# clock2x.net
KiCad netlist of a schematic drawn in EAGLE
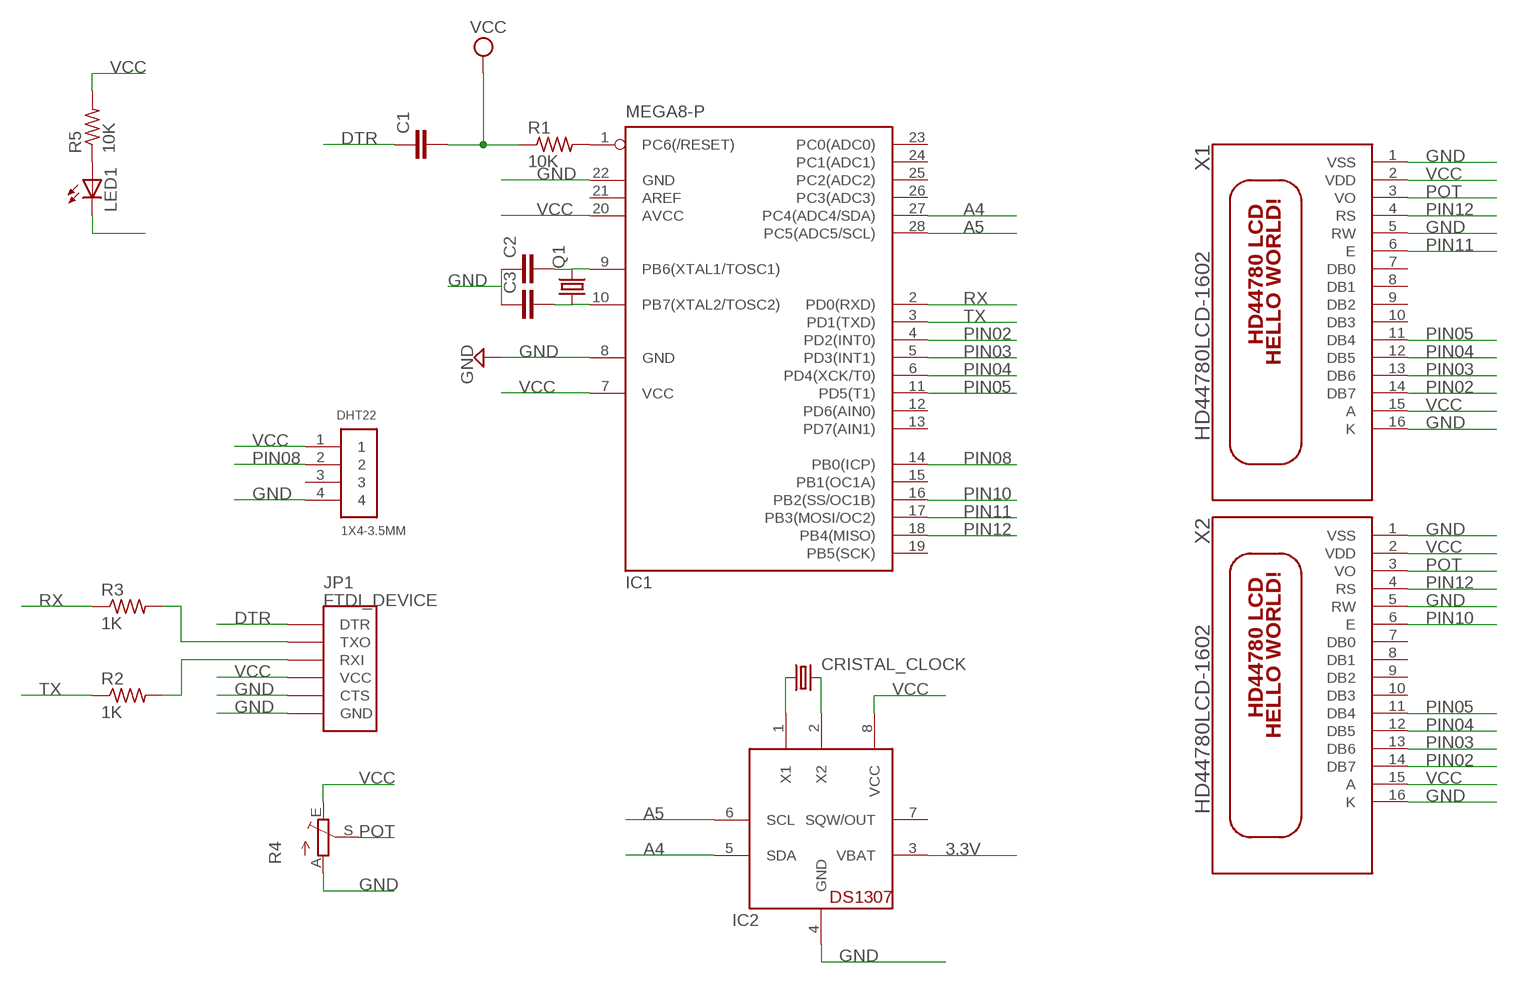
[diagram p0: schematic, sheet 1]

(export (version "E")
  (design (tool "Eeschema 10.0.6"))
  (components
    (comp (ref "C1")
      (value "C5/2.5")
      (footprint "eagle-import:C5B2.5")
      (libsource (lib "eagle-import") (part "C5/2.5"))
    )
    (comp (ref "C2")
      (value "C5/2.5")
      (footprint "eagle-import:C5B2.5")
      (libsource (lib "eagle-import") (part "C5/2.5"))
    )
    (comp (ref "C3")
      (value "C5/2.5")
      (footprint "eagle-import:C5B2.5")
      (libsource (lib "eagle-import") (part "C5/2.5"))
    )
    (comp (ref "CRISTAL_CLOCK")
      (value "CRYSTALTC26V")
      (footprint "eagle-import:TC26V")
      (libsource (lib "eagle-import") (part "CRYSTALTC26V"))
    )
    (comp (ref "DHT22")
      (value "1X4-3.5MM")
      (footprint "eagle-import:1X04-3.5MM")
      (libsource (lib "eagle-import") (part "1X4-3.5MM"))
    )
    (comp (ref "IC1")
      (value "MEGA8-P")
      (footprint "eagle-import:DIL28-3")
      (libsource (lib "eagle-import") (part "MEGA8-P"))
    )
    (comp (ref "IC2")
      (value "DS1307")
      (footprint "eagle-import:DIL08")
      (libsource (lib "eagle-import") (part "DS1307"))
    )
    (comp (ref "JP1")
      (value "FTDI_DEVICE")
      (footprint "eagle-import:FTDI_DEVICE_SIDE")
      (libsource (lib "eagle-import") (part "FTDI_DEVICE"))
    )
    (comp (ref "LED1")
      (value "LED5MM")
      (footprint "eagle-import:LED5MM")
      (libsource (lib "eagle-import") (part "LED5MM"))
    )
    (comp (ref "Q1")
      (value "CRYSTALHC49S")
      (footprint "eagle-import:HC49_S")
      (libsource (lib "eagle-import") (part "CRYSTALHC49S"))
    )
    (comp (ref "R1")
      (value "10K")
      (footprint "eagle-import:0207_12")
      (libsource (lib "eagle-import") (part "R-US_0207/12"))
    )
    (comp (ref "R2")
      (value "1K")
      (footprint "eagle-import:0207_12")
      (libsource (lib "eagle-import") (part "R-US_0207/12"))
    )
    (comp (ref "R3")
      (value "1K")
      (footprint "eagle-import:0207_12")
      (libsource (lib "eagle-import") (part "R-US_0207/12"))
    )
    (comp (ref "R4")
      (value "TRIM_EU-RJ9W")
      (footprint "eagle-import:RJ9W")
      (libsource (lib "eagle-import") (part "TRIM_EU-RJ9W"))
    )
    (comp (ref "R5")
      (value "10K")
      (footprint "eagle-import:0207_12")
      (libsource (lib "eagle-import") (part "R-US_0207/12"))
    )
    (comp (ref "X1")
      (value "HD44780LCD-1602")
      (footprint "eagle-import:LCD1602")
      (libsource (lib "eagle-import") (part "HD44780LCD-1602"))
    )
    (comp (ref "X2")
      (value "HD44780LCD-1602")
      (footprint "eagle-import:LCD1602")
      (libsource (lib "eagle-import") (part "HD44780LCD-1602"))
    )
  )
  (nets
    (net (code "1") (name "/3.3V") (class "Default")
      (node (ref "IC2") (pin "3") (pinfunction "VBAT_3") (pintype "power_in"))
    )
    (net (code "2") (name "/A4") (class "Default")
      (node (ref "IC1") (pin "27") (pinfunction "PC4(ADC4/SDA)_27") (pintype "bidirectional"))
      (node (ref "IC2") (pin "5") (pinfunction "SDA_5") (pintype "bidirectional"))
    )
    (net (code "3") (name "/A5") (class "Default")
      (node (ref "IC1") (pin "28") (pinfunction "PC5(ADC5/SCL)_28") (pintype "bidirectional"))
      (node (ref "IC2") (pin "6") (pinfunction "SCL_6") (pintype "bidirectional"))
    )
    (net (code "4") (name "/DTR") (class "Default")
      (node (ref "C1") (pin "1") (pinfunction "1_1") (pintype "passive"))
      (node (ref "JP1") (pin "P$1") (pinfunction "DTR_P$1") (pintype "bidirectional"))
    )
    (net (code "5") (name "/PIN02") (class "Default")
      (node (ref "IC1") (pin "4") (pinfunction "PD2(INT0)_4") (pintype "bidirectional"))
      (node (ref "X1") (pin "14") (pinfunction "DB7_14") (pintype "bidirectional"))
      (node (ref "X2") (pin "14") (pinfunction "DB7_14") (pintype "bidirectional"))
    )
    (net (code "6") (name "/PIN03") (class "Default")
      (node (ref "IC1") (pin "5") (pinfunction "PD3(INT1)_5") (pintype "bidirectional"))
      (node (ref "X1") (pin "13") (pinfunction "DB6_13") (pintype "bidirectional"))
      (node (ref "X2") (pin "13") (pinfunction "DB6_13") (pintype "bidirectional"))
    )
    (net (code "7") (name "/PIN04") (class "Default")
      (node (ref "IC1") (pin "6") (pinfunction "PD4(XCK/T0)_6") (pintype "bidirectional"))
      (node (ref "X1") (pin "12") (pinfunction "DB5_12") (pintype "bidirectional"))
      (node (ref "X2") (pin "12") (pinfunction "DB5_12") (pintype "bidirectional"))
    )
    (net (code "8") (name "/PIN05") (class "Default")
      (node (ref "IC1") (pin "11") (pinfunction "PD5(T1)_11") (pintype "bidirectional"))
      (node (ref "X1") (pin "11") (pinfunction "DB4_11") (pintype "bidirectional"))
      (node (ref "X2") (pin "11") (pinfunction "DB4_11") (pintype "bidirectional"))
    )
    (net (code "9") (name "/PIN08") (class "Default")
      (node (ref "DHT22") (pin "2") (pinfunction "2_2") (pintype "bidirectional"))
      (node (ref "IC1") (pin "14") (pinfunction "PB0(ICP)_14") (pintype "bidirectional"))
    )
    (net (code "10") (name "/PIN10") (class "Default")
      (node (ref "IC1") (pin "16") (pinfunction "PB2(SS/OC1B)_16") (pintype "bidirectional"))
      (node (ref "X2") (pin "6") (pinfunction "E_6") (pintype "input"))
    )
    (net (code "11") (name "/PIN11") (class "Default")
      (node (ref "IC1") (pin "17") (pinfunction "PB3(MOSI/OC2)_17") (pintype "bidirectional"))
      (node (ref "X1") (pin "6") (pinfunction "E_6") (pintype "input"))
    )
    (net (code "12") (name "/PIN12") (class "Default")
      (node (ref "IC1") (pin "18") (pinfunction "PB4(MISO)_18") (pintype "bidirectional"))
      (node (ref "X1") (pin "4") (pinfunction "RS_4") (pintype "input"))
      (node (ref "X2") (pin "4") (pinfunction "RS_4") (pintype "input"))
    )
    (net (code "13") (name "/POT") (class "Default")
      (node (ref "R4") (pin "S") (pinfunction "S_S") (pintype "passive"))
      (node (ref "X1") (pin "3") (pinfunction "VO_3") (pintype "input"))
      (node (ref "X2") (pin "3") (pinfunction "VO_3") (pintype "input"))
    )
    (net (code "14") (name "/RX") (class "Default")
      (node (ref "IC1") (pin "2") (pinfunction "PD0(RXD)_2") (pintype "bidirectional"))
      (node (ref "R3") (pin "1") (pinfunction "1_1") (pintype "passive"))
    )
    (net (code "15") (name "/TX") (class "Default")
      (node (ref "IC1") (pin "3") (pinfunction "PD1(TXD)_3") (pintype "bidirectional"))
      (node (ref "R2") (pin "1") (pinfunction "1_1") (pintype "passive"))
    )
    (net (code "16") (name "GND") (class "Default")
      (node (ref "C2") (pin "1") (pinfunction "1_1") (pintype "passive"))
      (node (ref "C3") (pin "1") (pinfunction "1_1") (pintype "passive"))
      (node (ref "DHT22") (pin "4") (pinfunction "4_4") (pintype "bidirectional"))
      (node (ref "IC1") (pin "22") (pinfunction "GND_22") (pintype "power_in"))
      (node (ref "IC1") (pin "8") (pinfunction "GND_8") (pintype "power_in"))
      (node (ref "IC2") (pin "4") (pinfunction "GND_4") (pintype "power_in"))
      (node (ref "JP1") (pin "P$5") (pinfunction "CTS_P$5") (pintype "bidirectional"))
      (node (ref "JP1") (pin "P$6") (pinfunction "GND_P$6") (pintype "bidirectional"))
      (node (ref "LED1") (pin "K") (pinfunction "C_K") (pintype "passive"))
      (node (ref "R4") (pin "A") (pinfunction "A_A") (pintype "passive"))
      (node (ref "X1") (pin "1") (pinfunction "VSS_1") (pintype "power_in"))
      (node (ref "X1") (pin "16") (pinfunction "K_16") (pintype "input"))
      (node (ref "X1") (pin "5") (pinfunction "RW_5") (pintype "input"))
      (node (ref "X2") (pin "1") (pinfunction "VSS_1") (pintype "power_in"))
      (node (ref "X2") (pin "16") (pinfunction "K_16") (pintype "input"))
      (node (ref "X2") (pin "5") (pinfunction "RW_5") (pintype "input"))
    )
    (net (code "17") (name "Net-(IC1-PB6(XTAL1{slash}TOSC1))") (class "Default")
      (node (ref "C2") (pin "2") (pinfunction "2_2") (pintype "passive"))
      (node (ref "IC1") (pin "9") (pinfunction "PB6(XTAL1/TOSC1)_9") (pintype "bidirectional"))
      (node (ref "Q1") (pin "2") (pinfunction "2_2") (pintype "passive"))
    )
    (net (code "18") (name "Net-(IC1-PB7(XTAL2{slash}TOSC2))") (class "Default")
      (node (ref "C3") (pin "2") (pinfunction "2_2") (pintype "passive"))
      (node (ref "IC1") (pin "10") (pinfunction "PB7(XTAL2/TOSC2)_10") (pintype "bidirectional"))
      (node (ref "Q1") (pin "1") (pinfunction "1_1") (pintype "passive"))
    )
    (net (code "19") (name "Net-(IC1-PC6({slash}RESET))") (class "Default")
      (node (ref "IC1") (pin "1") (pinfunction "PC6(/RESET)_1") (pintype "bidirectional"))
      (node (ref "R1") (pin "2") (pinfunction "2_2") (pintype "passive"))
    )
    (net (code "20") (name "Net-(IC2-X1)") (class "Default")
      (node (ref "CRISTAL_CLOCK") (pin "1") (pinfunction "1_1") (pintype "passive"))
      (node (ref "IC2") (pin "1") (pinfunction "X1_1") (pintype "passive"))
    )
    (net (code "21") (name "Net-(IC2-X2)") (class "Default")
      (node (ref "CRISTAL_CLOCK") (pin "2") (pinfunction "2_2") (pintype "passive"))
      (node (ref "IC2") (pin "2") (pinfunction "X2_2") (pintype "passive"))
    )
    (net (code "22") (name "Net-(JP1-RXI)") (class "Default")
      (node (ref "JP1") (pin "P$3") (pinfunction "RXI_P$3") (pintype "bidirectional"))
      (node (ref "R2") (pin "2") (pinfunction "2_2") (pintype "passive"))
    )
    (net (code "23") (name "Net-(JP1-TXO)") (class "Default")
      (node (ref "JP1") (pin "P$2") (pinfunction "TXO_P$2") (pintype "bidirectional"))
      (node (ref "R3") (pin "2") (pinfunction "2_2") (pintype "passive"))
    )
    (net (code "24") (name "Net-(LED1-PadA)") (class "Default")
      (node (ref "LED1") (pin "A") (pinfunction "A_A") (pintype "passive"))
      (node (ref "R5") (pin "1") (pinfunction "1_1") (pintype "passive"))
    )
    (net (code "25") (name "VCC") (class "Default")
      (node (ref "C1") (pin "2") (pinfunction "2_2") (pintype "passive"))
      (node (ref "DHT22") (pin "1") (pinfunction "1_1") (pintype "bidirectional"))
      (node (ref "IC1") (pin "20") (pinfunction "AVCC_20") (pintype "power_in"))
      (node (ref "IC1") (pin "7") (pinfunction "VCC_7") (pintype "power_in"))
      (node (ref "IC2") (pin "8") (pinfunction "VCC_8") (pintype "power_in"))
      (node (ref "JP1") (pin "P$4") (pinfunction "VCC_P$4") (pintype "bidirectional"))
      (node (ref "R1") (pin "1") (pinfunction "1_1") (pintype "passive"))
      (node (ref "R4") (pin "E") (pinfunction "E_E") (pintype "passive"))
      (node (ref "R5") (pin "2") (pinfunction "2_2") (pintype "passive"))
      (node (ref "X1") (pin "15") (pinfunction "A_15") (pintype "input"))
      (node (ref "X1") (pin "2") (pinfunction "VDD_2") (pintype "power_in"))
      (node (ref "X2") (pin "15") (pinfunction "A_15") (pintype "input"))
      (node (ref "X2") (pin "2") (pinfunction "VDD_2") (pintype "power_in"))
    )
    (net (code "26") (name "unconnected-(DHT22-Pad3)") (class "Default")
      (node (ref "DHT22") (pin "3") (pinfunction "3_3") (pintype "bidirectional"))
    )
    (net (code "27") (name "unconnected-(IC1-AREF-Pad21)") (class "Default")
      (node (ref "IC1") (pin "21") (pinfunction "AREF_21") (pintype "passive"))
    )
    (net (code "28") (name "unconnected-(IC1-PB1(OC1A)-Pad15)") (class "Default")
      (node (ref "IC1") (pin "15") (pinfunction "PB1(OC1A)_15") (pintype "bidirectional"))
    )
    (net (code "29") (name "unconnected-(IC1-PB5(SCK)-Pad19)") (class "Default")
      (node (ref "IC1") (pin "19") (pinfunction "PB5(SCK)_19") (pintype "bidirectional"))
    )
    (net (code "30") (name "unconnected-(IC1-PC0(ADC0)-Pad23)") (class "Default")
      (node (ref "IC1") (pin "23") (pinfunction "PC0(ADC0)_23") (pintype "bidirectional"))
    )
    (net (code "31") (name "unconnected-(IC1-PC1(ADC1)-Pad24)") (class "Default")
      (node (ref "IC1") (pin "24") (pinfunction "PC1(ADC1)_24") (pintype "bidirectional"))
    )
    (net (code "32") (name "unconnected-(IC1-PC2(ADC2)-Pad25)") (class "Default")
      (node (ref "IC1") (pin "25") (pinfunction "PC2(ADC2)_25") (pintype "bidirectional"))
    )
    (net (code "33") (name "unconnected-(IC1-PC3(ADC3)-Pad26)") (class "Default")
      (node (ref "IC1") (pin "26") (pinfunction "PC3(ADC3)_26") (pintype "bidirectional"))
    )
    (net (code "34") (name "unconnected-(IC1-PD6(AIN0)-Pad12)") (class "Default")
      (node (ref "IC1") (pin "12") (pinfunction "PD6(AIN0)_12") (pintype "bidirectional"))
    )
    (net (code "35") (name "unconnected-(IC1-PD7(AIN1)-Pad13)") (class "Default")
      (node (ref "IC1") (pin "13") (pinfunction "PD7(AIN1)_13") (pintype "bidirectional"))
    )
    (net (code "36") (name "unconnected-(IC2-SQW{slash}OUT-Pad7)") (class "Default")
      (node (ref "IC2") (pin "7") (pinfunction "SQW/OUT_7") (pintype "bidirectional"))
    )
    (net (code "37") (name "unconnected-(X1-DB0-Pad7)") (class "Default")
      (node (ref "X1") (pin "7") (pinfunction "DB0_7") (pintype "bidirectional"))
    )
    (net (code "38") (name "unconnected-(X1-DB1-Pad8)") (class "Default")
      (node (ref "X1") (pin "8") (pinfunction "DB1_8") (pintype "bidirectional"))
    )
    (net (code "39") (name "unconnected-(X1-DB2-Pad9)") (class "Default")
      (node (ref "X1") (pin "9") (pinfunction "DB2_9") (pintype "bidirectional"))
    )
    (net (code "40") (name "unconnected-(X1-DB3-Pad10)") (class "Default")
      (node (ref "X1") (pin "10") (pinfunction "DB3_10") (pintype "bidirectional"))
    )
    (net (code "41") (name "unconnected-(X2-DB0-Pad7)") (class "Default")
      (node (ref "X2") (pin "7") (pinfunction "DB0_7") (pintype "bidirectional"))
    )
    (net (code "42") (name "unconnected-(X2-DB1-Pad8)") (class "Default")
      (node (ref "X2") (pin "8") (pinfunction "DB1_8") (pintype "bidirectional"))
    )
    (net (code "43") (name "unconnected-(X2-DB2-Pad9)") (class "Default")
      (node (ref "X2") (pin "9") (pinfunction "DB2_9") (pintype "bidirectional"))
    )
    (net (code "44") (name "unconnected-(X2-DB3-Pad10)") (class "Default")
      (node (ref "X2") (pin "10") (pinfunction "DB3_10") (pintype "bidirectional"))
    )
  )
)
